# ETH.net
KiCad netlist of a schematic drawn in Altium Designer
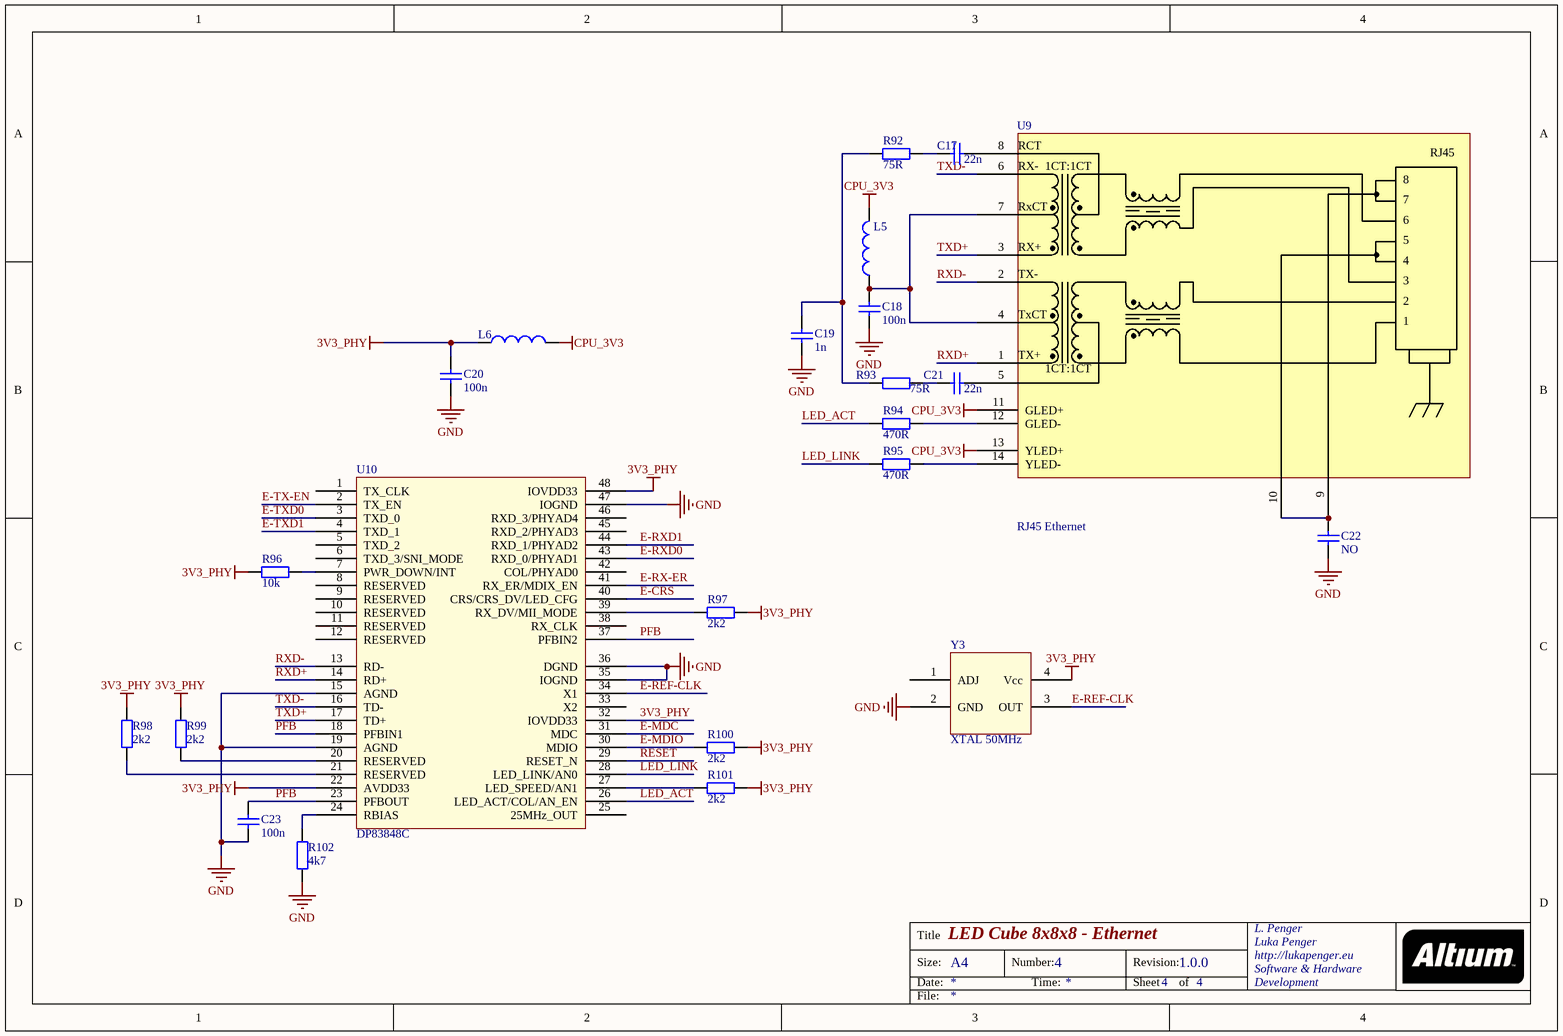
[diagram p0: ETH.SchDoc]

(export (version "E")
  (design (tool "Eeschema 10.0.6"))
  (components
    (comp (ref "C17")
      (value "22n")
      (footprint "1608[0603]")
      (description "Capacitor")
      (fields (field (name "PUBLISHER") "Altium Limited"))
      (libsource (lib "Miscellaneous Devices") (part "Cap"))
    )
    (comp (ref "C18")
      (value "100n")
      (footprint "1608[0603]")
      (description "Capacitor")
      (fields (field (name "PUBLISHER") "Altium Limited"))
      (libsource (lib "Miscellaneous Devices") (part "Cap"))
    )
    (comp (ref "C19")
      (value "1n")
      (footprint "1608[0603]")
      (description "Capacitor")
      (fields (field (name "PUBLISHER") "Altium Limited"))
      (libsource (lib "Miscellaneous Devices") (part "Cap"))
    )
    (comp (ref "C20")
      (value "100n")
      (footprint "1608[0603]")
      (description "Capacitor")
      (fields (field (name "PUBLISHER") "Altium Limited"))
      (libsource (lib "Miscellaneous Devices") (part "Cap"))
    )
    (comp (ref "C21")
      (value "22n")
      (footprint "1608[0603]")
      (description "Capacitor")
      (fields (field (name "PUBLISHER") "Altium Limited"))
      (libsource (lib "Miscellaneous Devices") (part "Cap"))
    )
    (comp (ref "C22")
      (value "NO")
      (footprint "1608[0603]")
      (description "Capacitor")
      (fields (field (name "PUBLISHER") "Altium Limited"))
      (libsource (lib "Miscellaneous Devices") (part "Cap"))
    )
    (comp (ref "C23")
      (value "100n")
      (footprint "6-0805_L")
      (description "Capacitor")
      (fields (field (name "PUBLISHER") "Altium Limited"))
      (libsource (lib "Miscellaneous Devices") (part "Cap"))
    )
    (comp (ref "L5")
      (value "Inductor")
      (footprint "1608[0603]")
      (fields (field (name "PUBLISHER") "Altium Limited"))
      (libsource (lib "Miscellaneous Devices") (part "Inductor"))
    )
    (comp (ref "L6")
      (value "Inductor")
      (footprint "1608[0603]")
      (fields (field (name "PUBLISHER") "Altium Limited"))
      (libsource (lib "Miscellaneous Devices") (part "Inductor"))
    )
    (comp (ref "R92")
      (value "75R")
      (footprint "1608[0603]")
      (description "Resistor")
      (fields (field (name "PUBLISHER") "Altium Limited"))
      (libsource (lib "Miscellaneous Devices") (part "Res2"))
    )
    (comp (ref "R93")
      (value "75R")
      (footprint "1608[0603]")
      (description "Resistor")
      (fields (field (name "PUBLISHER") "Altium Limited"))
      (libsource (lib "") (part "Res2_3"))
    )
    (comp (ref "R94")
      (value "470R")
      (footprint "1608[0603]")
      (description "Resistor")
      (fields (field (name "PUBLISHER") "Altium Limited"))
      (libsource (lib "Miscellaneous Devices") (part "Res2"))
    )
    (comp (ref "R95")
      (value "470R")
      (footprint "1608[0603]")
      (description "Resistor")
      (fields (field (name "PUBLISHER") "Altium Limited"))
      (libsource (lib "Miscellaneous Devices") (part "Res2"))
    )
    (comp (ref "R96")
      (value "10k")
      (footprint "1608[0603]")
      (description "Resistor")
      (fields (field (name "PUBLISHER") "Altium Limited"))
      (libsource (lib "Miscellaneous Devices") (part "Res2"))
    )
    (comp (ref "R97")
      (value "2k2")
      (footprint "1608[0603]")
      (description "Resistor")
      (fields (field (name "PUBLISHER") "Altium Limited"))
      (libsource (lib "Miscellaneous Devices") (part "Res2"))
    )
    (comp (ref "R98")
      (value "2k2")
      (footprint "1608[0603]")
      (description "Resistor")
      (fields (field (name "PUBLISHER") "Altium Limited"))
      (libsource (lib "") (part "Res2_1"))
    )
    (comp (ref "R99")
      (value "2k2")
      (footprint "1608[0603]")
      (description "Resistor")
      (fields (field (name "PUBLISHER") "Altium Limited"))
      (libsource (lib "") (part "Res2_2"))
    )
    (comp (ref "R100")
      (value "2k2")
      (footprint "1608[0603]")
      (description "Resistor")
      (fields (field (name "PUBLISHER") "Altium Limited"))
      (libsource (lib "Miscellaneous Devices") (part "Res2"))
    )
    (comp (ref "R101")
      (value "2k2")
      (footprint "1608[0603]")
      (description "Resistor")
      (fields (field (name "PUBLISHER") "Altium Limited"))
      (libsource (lib "Miscellaneous Devices") (part "Res2"))
    )
    (comp (ref "R102")
      (value "4k7")
      (footprint "1608[0603]")
      (description "Resistor")
      (fields (field (name "PUBLISHER") "Altium Limited"))
      (libsource (lib "") (part "Res2_1"))
    )
    (comp (ref "U9")
      (value "RJ45 Ethernet")
      (footprint "RJ45 Ethernet connector")
      (description "Ethernet Connector")
      (libsource (lib "LP_Lib") (part "RJ45 Ethernet"))
    )
    (comp (ref "U10")
      (value "DP83848C")
      (footprint "DP83848C")
      (description "Ethernet PHY")
      (libsource (lib "LP_Lib") (part "DP83848C"))
    )
    (comp (ref "Y3")
      (value "XTAL 50MHz")
      (footprint "XTAL ACT9200")
      (libsource (lib "LP_Lib") (part "XTAL ACT9200"))
    )
  )
  (nets
    (net (code "1") (name "/E-CRS") (class "Default")
      (node (ref "U10") (pin "40") (pinfunction "CRS/CRS_DV/LED_CFG_40") (pintype "passive"))
    )
    (net (code "2") (name "/E-MDC") (class "Default")
      (node (ref "U10") (pin "31") (pinfunction "MDC_31") (pintype "passive"))
    )
    (net (code "3") (name "/E-MDIO") (class "Default")
      (node (ref "R100") (pin "2") (pinfunction "2_2") (pintype "passive"))
      (node (ref "U10") (pin "30") (pinfunction "MDIO_30") (pintype "passive"))
    )
    (net (code "4") (name "/E-REF-CLK") (class "Default")
      (node (ref "U10") (pin "34") (pinfunction "X1_34") (pintype "passive"))
      (node (ref "Y3") (pin "3") (pinfunction "OUT_3") (pintype "passive"))
    )
    (net (code "5") (name "/E-RX-ER") (class "Default")
      (node (ref "U10") (pin "41") (pinfunction "RX_ER/MDIX_EN_41") (pintype "passive"))
    )
    (net (code "6") (name "/E-RXD0") (class "Default")
      (node (ref "U10") (pin "43") (pinfunction "RXD_0/PHYAD1_43") (pintype "passive"))
    )
    (net (code "7") (name "/E-RXD1") (class "Default")
      (node (ref "U10") (pin "44") (pinfunction "RXD_1/PHYAD2_44") (pintype "passive"))
    )
    (net (code "8") (name "/E-TX-EN") (class "Default")
      (node (ref "U10") (pin "2") (pinfunction "TX_EN_2") (pintype "passive"))
    )
    (net (code "9") (name "/E-TXD0") (class "Default")
      (node (ref "U10") (pin "3") (pinfunction "TXD_0_3") (pintype "passive"))
    )
    (net (code "10") (name "/E-TXD1") (class "Default")
      (node (ref "U10") (pin "4") (pinfunction "TXD_1_4") (pintype "passive"))
    )
    (net (code "11") (name "/LED_ACT") (class "Default")
      (node (ref "R94") (pin "2") (pinfunction "2_2") (pintype "passive"))
      (node (ref "U10") (pin "26") (pinfunction "LED_ACT/COL/AN_EN_26") (pintype "passive"))
    )
    (net (code "12") (name "/LED_LINK") (class "Default")
      (node (ref "R95") (pin "2") (pinfunction "2_2") (pintype "passive"))
      (node (ref "U10") (pin "28") (pinfunction "LED_LINK/AN0_28") (pintype "passive"))
    )
    (net (code "13") (name "/PFB") (class "Default")
      (node (ref "C23") (pin "1") (pinfunction "1_1") (pintype "passive"))
      (node (ref "U10") (pin "18") (pinfunction "PFBIN1_18") (pintype "passive"))
      (node (ref "U10") (pin "23") (pinfunction "PFBOUT_23") (pintype "passive"))
      (node (ref "U10") (pin "37") (pinfunction "PFBIN2_37") (pintype "passive"))
    )
    (net (code "14") (name "/RXD+") (class "Default")
      (node (ref "U10") (pin "14") (pinfunction "RD+_14") (pintype "passive"))
      (node (ref "U9") (pin "1") (pintype "passive"))
    )
    (net (code "15") (name "/RXD-") (class "Default")
      (node (ref "U10") (pin "13") (pinfunction "RD-_13") (pintype "passive"))
      (node (ref "U9") (pin "2") (pintype "passive"))
    )
    (net (code "16") (name "/TXD+") (class "Default")
      (node (ref "U10") (pin "17") (pinfunction "TD+_17") (pintype "passive"))
      (node (ref "U9") (pin "3") (pintype "passive"))
    )
    (net (code "17") (name "/TXD-") (class "Default")
      (node (ref "U10") (pin "16") (pinfunction "TD-_16") (pintype "passive"))
      (node (ref "U9") (pin "6") (pintype "passive"))
    )
    (net (code "18") (name "/~{RESET}") (class "Default")
      (node (ref "U10") (pin "29") (pinfunction "RESET_N_29") (pintype "passive"))
    )
    (net (code "19") (name "3V3_PHY") (class "Default")
      (node (ref "C20") (pin "1") (pinfunction "1_1") (pintype "passive"))
      (node (ref "L6") (pin "1") (pinfunction "1_1") (pintype "passive"))
      (node (ref "R100") (pin "1") (pinfunction "1_1") (pintype "passive"))
      (node (ref "R101") (pin "1") (pinfunction "1_1") (pintype "passive"))
      (node (ref "R96") (pin "2") (pinfunction "2_2") (pintype "passive"))
      (node (ref "R97") (pin "1") (pinfunction "1_1") (pintype "passive"))
      (node (ref "R98") (pin "1") (pinfunction "1_1") (pintype "passive"))
      (node (ref "R99") (pin "2") (pinfunction "2_2") (pintype "passive"))
      (node (ref "U10") (pin "22") (pinfunction "AVDD33_22") (pintype "passive"))
      (node (ref "U10") (pin "32") (pinfunction "IOVDD33_32") (pintype "passive"))
      (node (ref "U10") (pin "48") (pinfunction "IOVDD33_48") (pintype "passive"))
      (node (ref "Y3") (pin "4") (pinfunction "Vcc_4") (pintype "passive"))
    )
    (net (code "20") (name "CPU_3V3") (class "Default")
      (node (ref "L5") (pin "2") (pinfunction "2_2") (pintype "passive"))
      (node (ref "L6") (pin "2") (pinfunction "2_2") (pintype "passive"))
      (node (ref "U9") (pin "11") (pinfunction "GLED+_11") (pintype "passive"))
      (node (ref "U9") (pin "13") (pinfunction "YLED+_13") (pintype "passive"))
    )
    (net (code "21") (name "GND") (class "Default")
      (node (ref "C18") (pin "2") (pinfunction "2_2") (pintype "passive"))
      (node (ref "C19") (pin "2") (pinfunction "2_2") (pintype "passive"))
      (node (ref "C20") (pin "2") (pinfunction "2_2") (pintype "passive"))
      (node (ref "C22") (pin "1") (pinfunction "1_1") (pintype "passive"))
      (node (ref "C23") (pin "2") (pinfunction "2_2") (pintype "passive"))
      (node (ref "R102") (pin "2") (pinfunction "2_2") (pintype "passive"))
      (node (ref "U10") (pin "15") (pinfunction "AGND_15") (pintype "passive"))
      (node (ref "U10") (pin "19") (pinfunction "AGND_19") (pintype "passive"))
      (node (ref "U10") (pin "35") (pinfunction "IOGND_35") (pintype "passive"))
      (node (ref "U10") (pin "36") (pinfunction "DGND_36") (pintype "passive"))
      (node (ref "U10") (pin "47") (pinfunction "IOGND_47") (pintype "passive"))
      (node (ref "Y3") (pin "2") (pinfunction "GND_2") (pintype "passive"))
    )
    (net (code "22") (name "Net-(C17-Pad1)") (class "Default")
      (node (ref "C17") (pin "1") (pinfunction "1_1") (pintype "passive"))
      (node (ref "U9") (pin "8") (pintype "passive"))
    )
    (net (code "23") (name "Net-(C17-Pad2)") (class "Default")
      (node (ref "C17") (pin "2") (pinfunction "2_2") (pintype "passive"))
      (node (ref "R92") (pin "1") (pinfunction "1_1") (pintype "passive"))
    )
    (net (code "24") (name "Net-(C18-Pad1)") (class "Default")
      (node (ref "C18") (pin "1") (pinfunction "1_1") (pintype "passive"))
      (node (ref "L5") (pin "1") (pinfunction "1_1") (pintype "passive"))
      (node (ref "U9") (pin "4") (pintype "passive"))
      (node (ref "U9") (pin "7") (pintype "passive"))
    )
    (net (code "25") (name "Net-(C19-Pad1)") (class "Default")
      (node (ref "C19") (pin "1") (pinfunction "1_1") (pintype "passive"))
      (node (ref "R92") (pin "2") (pinfunction "2_2") (pintype "passive"))
      (node (ref "R93") (pin "1") (pinfunction "1_1") (pintype "passive"))
    )
    (net (code "26") (name "Net-(C21-Pad1)") (class "Default")
      (node (ref "C21") (pin "1") (pinfunction "1_1") (pintype "passive"))
      (node (ref "U9") (pin "5") (pintype "passive"))
    )
    (net (code "27") (name "Net-(C21-Pad2)") (class "Default")
      (node (ref "C21") (pin "2") (pinfunction "2_2") (pintype "passive"))
      (node (ref "R93") (pin "2") (pinfunction "2_2") (pintype "passive"))
    )
    (net (code "28") (name "Net-(C22-Pad2)") (class "Default")
      (node (ref "C22") (pin "2") (pinfunction "2_2") (pintype "passive"))
      (node (ref "U9") (pin "10") (pintype "passive"))
      (node (ref "U9") (pin "9") (pintype "passive"))
    )
    (net (code "29") (name "Net-(R98-Pad2)") (class "Default")
      (node (ref "R98") (pin "2") (pinfunction "2_2") (pintype "passive"))
      (node (ref "U10") (pin "21") (pinfunction "RESERVED_21") (pintype "passive"))
    )
    (net (code "30") (name "Net-(R99-Pad1)") (class "Default")
      (node (ref "R99") (pin "1") (pinfunction "1_1") (pintype "passive"))
      (node (ref "U10") (pin "20") (pinfunction "RESERVED_20") (pintype "passive"))
    )
    (net (code "31") (name "Net-(U9-GLED-)") (class "Default")
      (node (ref "R94") (pin "1") (pinfunction "1_1") (pintype "passive"))
      (node (ref "U9") (pin "12") (pinfunction "GLED-_12") (pintype "passive"))
    )
    (net (code "32") (name "Net-(U9-YLED-)") (class "Default")
      (node (ref "R95") (pin "1") (pinfunction "1_1") (pintype "passive"))
      (node (ref "U9") (pin "14") (pinfunction "YLED-_14") (pintype "passive"))
    )
    (net (code "33") (name "Net-(U10-LED_SPEED{slash}AN1)") (class "Default")
      (node (ref "R101") (pin "2") (pinfunction "2_2") (pintype "passive"))
      (node (ref "U10") (pin "27") (pinfunction "LED_SPEED/AN1_27") (pintype "passive"))
    )
    (net (code "34") (name "Net-(U10-PWR_DOWN{slash}INT)") (class "Default")
      (node (ref "R96") (pin "1") (pinfunction "1_1") (pintype "passive"))
      (node (ref "U10") (pin "7") (pinfunction "PWR_DOWN/INT_7") (pintype "passive"))
    )
    (net (code "35") (name "Net-(U10-RBIAS)") (class "Default")
      (node (ref "R102") (pin "1") (pinfunction "1_1") (pintype "passive"))
      (node (ref "U10") (pin "24") (pinfunction "RBIAS_24") (pintype "passive"))
    )
    (net (code "36") (name "Net-(U10-RX_DV{slash}MII_MODE)") (class "Default")
      (node (ref "R97") (pin "2") (pinfunction "2_2") (pintype "passive"))
      (node (ref "U10") (pin "39") (pinfunction "RX_DV/MII_MODE_39") (pintype "passive"))
    )
    (net (code "37") (name "unconnected-(U10-25MHz_OUT-Pad25)") (class "Default")
      (node (ref "U10") (pin "25") (pinfunction "25MHz_OUT_25") (pintype "passive"))
    )
    (net (code "38") (name "unconnected-(U10-COL{slash}PHYAD0-Pad42)") (class "Default")
      (node (ref "U10") (pin "42") (pinfunction "COL/PHYAD0_42") (pintype "passive"))
    )
    (net (code "39") (name "unconnected-(U10-RESERVED-Pad8)") (class "Default")
      (node (ref "U10") (pin "8") (pinfunction "RESERVED_8") (pintype "passive"))
    )
    (net (code "40") (name "unconnected-(U10-RESERVED-Pad9)") (class "Default")
      (node (ref "U10") (pin "9") (pinfunction "RESERVED_9") (pintype "passive"))
    )
    (net (code "41") (name "unconnected-(U10-RESERVED-Pad10)") (class "Default")
      (node (ref "U10") (pin "10") (pinfunction "RESERVED_10") (pintype "passive"))
    )
    (net (code "42") (name "unconnected-(U10-RESERVED-Pad11)") (class "Default")
      (node (ref "U10") (pin "11") (pinfunction "RESERVED_11") (pintype "passive"))
    )
    (net (code "43") (name "unconnected-(U10-RESERVED-Pad12)") (class "Default")
      (node (ref "U10") (pin "12") (pinfunction "RESERVED_12") (pintype "passive"))
    )
    (net (code "44") (name "unconnected-(U10-RXD_2{slash}PHYAD3-Pad45)") (class "Default")
      (node (ref "U10") (pin "45") (pinfunction "RXD_2/PHYAD3_45") (pintype "passive"))
    )
    (net (code "45") (name "unconnected-(U10-RXD_3{slash}PHYAD4-Pad46)") (class "Default")
      (node (ref "U10") (pin "46") (pinfunction "RXD_3/PHYAD4_46") (pintype "passive"))
    )
    (net (code "46") (name "unconnected-(U10-RX_CLK-Pad38)") (class "Default")
      (node (ref "U10") (pin "38") (pinfunction "RX_CLK_38") (pintype "passive"))
    )
    (net (code "47") (name "unconnected-(U10-TXD_2-Pad5)") (class "Default")
      (node (ref "U10") (pin "5") (pinfunction "TXD_2_5") (pintype "passive"))
    )
    (net (code "48") (name "unconnected-(U10-TXD_3{slash}SNI_MODE-Pad6)") (class "Default")
      (node (ref "U10") (pin "6") (pinfunction "TXD_3/SNI_MODE_6") (pintype "passive"))
    )
    (net (code "49") (name "unconnected-(U10-TX_CLK-Pad1)") (class "Default")
      (node (ref "U10") (pin "1") (pinfunction "TX_CLK_1") (pintype "passive"))
    )
    (net (code "50") (name "unconnected-(U10-X2-Pad33)") (class "Default")
      (node (ref "U10") (pin "33") (pinfunction "X2_33") (pintype "passive"))
    )
    (net (code "51") (name "unconnected-(Y3-ADJ-Pad1)") (class "Default")
      (node (ref "Y3") (pin "1") (pinfunction "ADJ_1") (pintype "passive"))
    )
  )
)
